# MC21R01_Inverter_2.net
KiCad netlist of a schematic drawn in Altium Designer
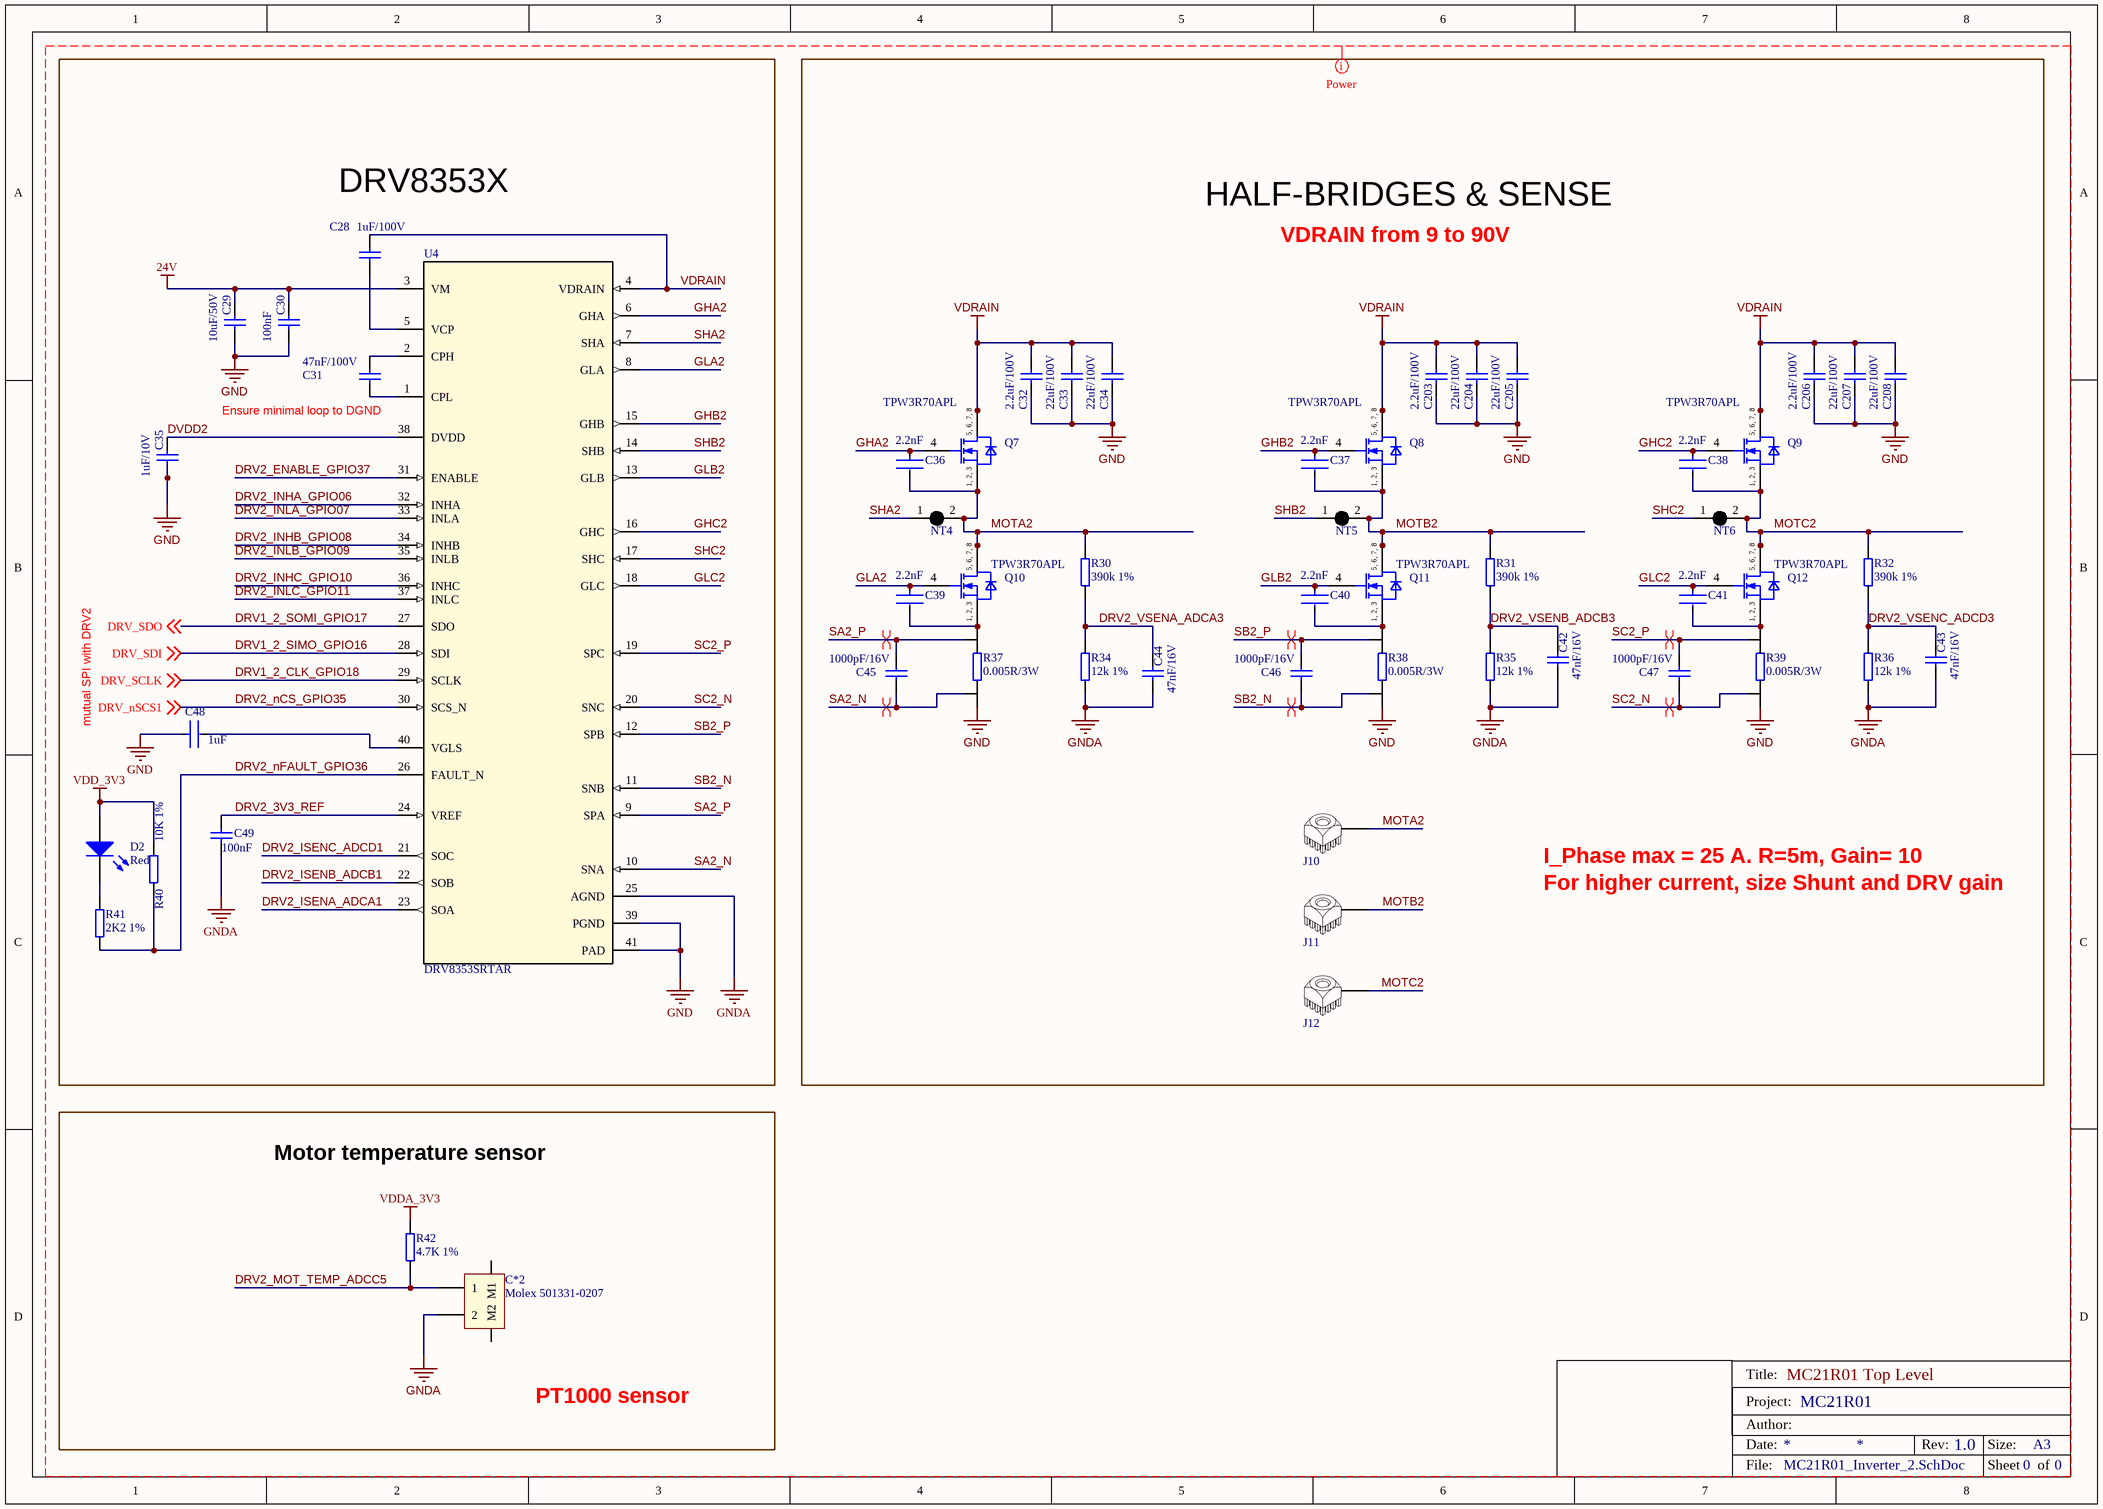
[diagram p0: MC21R01_Inverter_2.SchDoc]

(export (version "E")
  (design (tool "Eeschema 10.0.6"))
  (components
    (comp (ref "C*2")
      (value "Molex 501331-0207")
      (footprint "Molex 501331-0207")
      (description "PicoClasp 02 pin vertical")
      (libsource (lib "PAL_Molex") (part "Molex 501331-0207"))
    )
    (comp (ref "C28")
      (value "1uF/100V")
      (footprint "PAL_Capacitors:0805 SMD capacitor")
      (description "1 uF 100 V 0805  ±10% Tolerance X7R Multilayer Ceramic Chip Capacitor")
      (fields (field (name "Comment") "1uF/100V 0805 10% X7R"))
      (libsource (lib "PAL_Capacitors") (part "1uF/100V 0805 10% X7R"))
    )
    (comp (ref "C29")
      (value "10uF/50V")
      (footprint "PAL_Capacitors:1206 SMD Capacitor")
      (description "10 uF 50 V 1206 ±20% Tolerance X5R Multilayer Ceramic Chip Capacitor")
      (fields (field (name "Comment") "10uf/50V 1206 20% X5R"))
      (libsource (lib "PAL_Capacitors") (part "10uF/50V 1206 20% X5R"))
    )
    (comp (ref "C30")
      (value "100nF")
      (footprint "CAPC0603X03N")
      (description "100nF/25V 0201 10% Tolerance X6S Multilayer Ceramic Chip Capacitor")
      (fields (field (name "TOLERANCE") "10%") (field (name "Comment") "100nF/25V 0201 10% X6S"))
      (libsource (lib "Wandercraft") (part "STD_CAP_2PIN_NPOL"))
    )
    (comp (ref "C31")
      (value "47nF/100V")
      (footprint "PAL_Capacitors:0603 SMD capacitor")
      (description "47 nF 100 V 0603 ±10% Tolerance X7R Multilayer Ceramic Chip Capacitor")
      (fields (field (name "Comment") "47nF/100V 0603 10% X7R"))
      (libsource (lib "PAL_Capacitors") (part "47nF/100V 0603 10% X7R_1"))
    )
    (comp (ref "C32")
      (value "2.2uF/100V")
      (footprint "1210 SMD capacitor h=2mm")
      (description "2.2 uF 100 V 1210  ±10% Tolerance X7R Multilayer Ceramic Chip Capacitor")
      (fields (field (name "Comment") "2.2uF/100V 1210 10% X7R"))
      (libsource (lib "PAL_Capacitors") (part "2.2uF/100V 1210 10% X7R"))
    )
    (comp (ref "C33")
      (value "22uF/100V")
      (footprint "PAL_Capacitors:2220 SMD Capacitor H=5MM")
      (description "22 uF 100 V 2220 ±20% Tolerance X7S Multilayer Ceramic Chip Capacitor")
      (fields (field (name "Comment") "22uF/100V 2220 20% X7S"))
      (libsource (lib "PAL_Capacitors") (part "22uF/100V 2220 20% X7S"))
    )
    (comp (ref "C34")
      (value "22uF/100V")
      (footprint "PAL_Capacitors:2220 SMD Capacitor H=5MM")
      (description "22 uF 100 V 2220 ±20% Tolerance X7S Multilayer Ceramic Chip Capacitor")
      (fields (field (name "Comment") "22uF/100V 2220 20% X7S"))
      (libsource (lib "PAL_Capacitors") (part "22uF/100V 2220 20% X7S"))
    )
    (comp (ref "C35")
      (value "1uF/10V")
      (footprint "PAL_Capacitors:0603 SMD capacitor")
      (description "1uF/10V 0603 10% Tolerance X7R Multilayer Ceramic Chip Capacitor")
      (fields (field (name "Comment") "1uF/10V 0603 10% X7R"))
      (libsource (lib "PAL_Capacitors") (part "1uF/10V 0603 10% X7R"))
    )
    (comp (ref "C36")
      (value "2200pF/50V 0201 10% X7R")
      (footprint "FP-GRM033-0_03-IPC_A")
      (description "2200pF/50V 0201 10% Tolerance X7R Multilayer Ceramic Chip Capacitor")
      (fields (field (name "TOLERANCE") "10%") (field (name "CAPACITANCE") "2.2nF"))
      (libsource (lib "Altium Content Vault") (part "b4654b650e69147ec39a6b967a45e02"))
    )
    (comp (ref "C37")
      (value "2200pF/50V 0201 10% X7R")
      (footprint "FP-GRM033-0_03-IPC_A")
      (description "2200pF/50V 0201 10% Tolerance X7R Multilayer Ceramic Chip Capacitor")
      (fields (field (name "TOLERANCE") "10%") (field (name "CAPACITANCE") "2.2nF"))
      (libsource (lib "Altium Content Vault") (part "b4654b650e69147ec39a6b967a45e02"))
    )
    (comp (ref "C38")
      (value "2200pF/50V 0201 10% X7R")
      (footprint "FP-GRM033-0_03-IPC_A")
      (description "2200pF/50V 0201 10% Tolerance X7R Multilayer Ceramic Chip Capacitor")
      (fields (field (name "TOLERANCE") "10%") (field (name "CAPACITANCE") "2.2nF"))
      (libsource (lib "Altium Content Vault") (part "b4654b650e69147ec39a6b967a45e02"))
    )
    (comp (ref "C39")
      (value "2200pF/50V 0201 10% X7R")
      (footprint "FP-GRM033-0_03-IPC_A")
      (description "2200pF/50V 0201 10% Tolerance X7R Multilayer Ceramic Chip Capacitor")
      (fields (field (name "TOLERANCE") "10%") (field (name "CAPACITANCE") "2.2nF"))
      (libsource (lib "Altium Content Vault") (part "b4654b650e69147ec39a6b967a45e02"))
    )
    (comp (ref "C40")
      (value "2200pF/50V 0201 10% X7R")
      (footprint "FP-GRM033-0_03-IPC_A")
      (description "2200pF/50V 0201 10% Tolerance X7R Multilayer Ceramic Chip Capacitor")
      (fields (field (name "TOLERANCE") "10%") (field (name "CAPACITANCE") "2.2nF"))
      (libsource (lib "Altium Content Vault") (part "b4654b650e69147ec39a6b967a45e02"))
    )
    (comp (ref "C41")
      (value "2200pF/50V 0201 10% X7R")
      (footprint "FP-GRM033-0_03-IPC_A")
      (description "2200pF/50V 0201 10% Tolerance X7R Multilayer Ceramic Chip Capacitor")
      (fields (field (name "TOLERANCE") "10%") (field (name "CAPACITANCE") "2.2nF"))
      (libsource (lib "Altium Content Vault") (part "b4654b650e69147ec39a6b967a45e02"))
    )
    (comp (ref "C42")
      (value "47nF/16V")
      (footprint "PAL_Capacitors:0402 SMD Capacitor")
      (description "47nF/16V 0402 10% Tolerance X7R Multilayer Ceramic Chip Capacitor")
      (fields (field (name "Comment") "47nF/16V 0402 10% X7R"))
      (libsource (lib "PAL_Capacitors") (part "47nF/16V 0402 10% X7R"))
    )
    (comp (ref "C43")
      (value "47nF/16V")
      (footprint "PAL_Capacitors:0402 SMD Capacitor")
      (description "47nF/16V 0402 10% Tolerance X7R Multilayer Ceramic Chip Capacitor")
      (fields (field (name "Comment") "47nF/16V 0402 10% X7R"))
      (libsource (lib "PAL_Capacitors") (part "47nF/16V 0402 10% X7R"))
    )
    (comp (ref "C44")
      (value "47nF/16V")
      (footprint "PAL_Capacitors:0402 SMD Capacitor")
      (description "47nF/16V 0402 10% Tolerance X7R Multilayer Ceramic Chip Capacitor")
      (fields (field (name "Comment") "47nF/16V 0402 10% X7R"))
      (libsource (lib "PAL_Capacitors") (part "47nF/16V 0402 10% X7R"))
    )
    (comp (ref "C45")
      (value "1000pF/16V")
      (footprint "PAL_Capacitors:0402 SMD Capacitor")
      (description "1000pF/16V 0402 10% Tolerance X7R Multilayer Ceramic Chip Capacitor")
      (fields (field (name "Comment") "1000pF/16V 0402 10% X7R"))
      (libsource (lib "PAL_Capacitors") (part "1000pF/16V 0402 10% X7R_1"))
    )
    (comp (ref "C46")
      (value "1000pF/16V")
      (footprint "PAL_Capacitors:0402 SMD Capacitor")
      (description "1000pF/16V 0402 10% Tolerance X7R Multilayer Ceramic Chip Capacitor")
      (fields (field (name "Comment") "1000pF/16V 0402 10% X7R"))
      (libsource (lib "PAL_Capacitors") (part "1000pF/16V 0402 10% X7R_1"))
    )
    (comp (ref "C47")
      (value "1000pF/16V")
      (footprint "PAL_Capacitors:0402 SMD Capacitor")
      (description "1000pF/16V 0402 10% Tolerance X7R Multilayer Ceramic Chip Capacitor")
      (fields (field (name "Comment") "1000pF/16V 0402 10% X7R"))
      (libsource (lib "PAL_Capacitors") (part "1000pF/16V 0402 10% X7R_1"))
    )
    (comp (ref "C48")
      (value "1uF/6.3V 0201 10% X5R")
      (footprint "FP-CL03-IPC_A")
      (description "1uF/6.3V 0201 10% Tolerance X5R Multilayer Ceramic Chip Capacitor")
      (fields (field (name "TOLERANCE") "20%") (field (name "CAPACITANCE") "1uF"))
      (libsource (lib "Altium Content Vault") (part "b4654b650e69147ec39a6b967a45e02"))
    )
    (comp (ref "C49")
      (value "100nF")
      (footprint "CAPC0603X03N")
      (description "100nF/25V 0201 10% Tolerance X6S Multilayer Ceramic Chip Capacitor")
      (fields (field (name "TOLERANCE") "10%") (field (name "Comment") "100nF/25V 0201 10% X6S"))
      (libsource (lib "Wandercraft") (part "STD_CAP_2PIN_NPOL"))
    )
    (comp (ref "C203")
      (value "2.2uF/100V")
      (footprint "1210 SMD capacitor h=2mm")
      (description "2.2 uF 100 V 1210  ±10% Tolerance X7R Multilayer Ceramic Chip Capacitor")
      (fields (field (name "Comment") "2.2uF/100V 1210 10% X7R"))
      (libsource (lib "PAL_Capacitors") (part "2.2uF/100V 1210 10% X7R"))
    )
    (comp (ref "C204")
      (value "22uF/100V")
      (footprint "PAL_Capacitors:2220 SMD Capacitor H=5MM")
      (description "22 uF 100 V 2220 ±20% Tolerance X7S Multilayer Ceramic Chip Capacitor")
      (fields (field (name "Comment") "22uF/100V 2220 20% X7S"))
      (libsource (lib "PAL_Capacitors") (part "22uF/100V 2220 20% X7S"))
    )
    (comp (ref "C205")
      (value "22uF/100V")
      (footprint "PAL_Capacitors:2220 SMD Capacitor H=5MM")
      (description "22 uF 100 V 2220 ±20% Tolerance X7S Multilayer Ceramic Chip Capacitor")
      (fields (field (name "Comment") "22uF/100V 2220 20% X7S"))
      (libsource (lib "PAL_Capacitors") (part "22uF/100V 2220 20% X7S"))
    )
    (comp (ref "C206")
      (value "2.2uF/100V")
      (footprint "1210 SMD capacitor h=2mm")
      (description "2.2 uF 100 V 1210  ±10% Tolerance X7R Multilayer Ceramic Chip Capacitor")
      (fields (field (name "Comment") "2.2uF/100V 1210 10% X7R"))
      (libsource (lib "PAL_Capacitors") (part "2.2uF/100V 1210 10% X7R"))
    )
    (comp (ref "C207")
      (value "22uF/100V")
      (footprint "PAL_Capacitors:2220 SMD Capacitor H=5MM")
      (description "22 uF 100 V 2220 ±20% Tolerance X7S Multilayer Ceramic Chip Capacitor")
      (fields (field (name "Comment") "22uF/100V 2220 20% X7S"))
      (libsource (lib "PAL_Capacitors") (part "22uF/100V 2220 20% X7S"))
    )
    (comp (ref "C208")
      (value "22uF/100V")
      (footprint "PAL_Capacitors:2220 SMD Capacitor H=5MM")
      (description "22 uF 100 V 2220 ±20% Tolerance X7S Multilayer Ceramic Chip Capacitor")
      (fields (field (name "Comment") "22uF/100V 2220 20% X7S"))
      (libsource (lib "PAL_Capacitors") (part "22uF/100V 2220 20% X7S"))
    )
    (comp (ref "D2")
      (value "Red")
      (footprint "0402 SMD LED Red")
      (description "Low Profile Chip LED, Red")
      (fields (field (name "MANUFACTURER") "ROHM") (field (name "MANUFACTURER PART NUMBER") "SML-P11UTT86R"))
      (libsource (lib "PAL_devices") (part "LED_0402_Red"))
    )
    (comp (ref "J10")
      (value "WE_7461094")
      (footprint "WE_7461094")
      (description "REDCUBE PRESS-FIT with external thread and full plain pin-plate WPSHFU, 130A, M3 screw, 9pins")
      (fields
        (field (name "MANUFACTURER") "WURTH ELEKTRONIK")
        (field (name "MANUFACTURER PART NUMBER") "7461094")
        (field (name "CREATED BY") "Yaiza Montes")
      )
      (libsource (lib "PAL_Wurth_2020") (part "WE_7461094"))
    )
    (comp (ref "J11")
      (value "WE_7461094")
      (footprint "WE_7461094")
      (description "REDCUBE PRESS-FIT with external thread and full plain pin-plate WPSHFU, 130A, M3 screw, 9pins")
      (fields
        (field (name "MANUFACTURER") "WURTH ELEKTRONIK")
        (field (name "MANUFACTURER PART NUMBER") "7461094")
        (field (name "CREATED BY") "Yaiza Montes")
      )
      (libsource (lib "PAL_Wurth_2020") (part "WE_7461094"))
    )
    (comp (ref "J12")
      (value "WE_7461094")
      (footprint "WE_7461094")
      (description "REDCUBE PRESS-FIT with external thread and full plain pin-plate WPSHFU, 130A, M3 screw, 9pins")
      (fields
        (field (name "MANUFACTURER") "WURTH ELEKTRONIK")
        (field (name "MANUFACTURER PART NUMBER") "7461094")
        (field (name "CREATED BY") "Yaiza Montes")
      )
      (libsource (lib "PAL_Wurth_2020") (part "WE_7461094"))
    )
    (comp (ref "NT4")
      (value "Net Tie SMD")
      (footprint "PAL_devices:Net Tie SMD 0.4x0.8mm")
      (description "Net Tie starpoint")
      (libsource (lib "PAL_devices") (part "Net Tie SMD"))
    )
    (comp (ref "NT5")
      (value "Net Tie SMD")
      (footprint "PAL_devices:Net Tie SMD 0.4x0.8mm")
      (description "Net Tie starpoint")
      (libsource (lib "PAL_devices") (part "Net Tie SMD"))
    )
    (comp (ref "NT6")
      (value "Net Tie SMD")
      (footprint "PAL_devices:Net Tie SMD 0.4x0.8mm")
      (description "Net Tie starpoint")
      (libsource (lib "PAL_devices") (part "Net Tie SMD"))
    )
    (comp (ref "Q7")
      (value "TPW3R70APL")
      (footprint "DSOP Advance Toshiba")
      (description "Silicon N-channel MOS (U-MOS-H)")
      (fields (field (name "MANUFACTURER") "Toshiba Semicon"))
      (libsource (lib "PAL_devices") (part "TPW3R70APL"))
    )
    (comp (ref "Q8")
      (value "TPW3R70APL")
      (footprint "DSOP Advance Toshiba")
      (description "Silicon N-channel MOS (U-MOS-H)")
      (fields (field (name "MANUFACTURER") "Toshiba Semicon"))
      (libsource (lib "PAL_devices") (part "TPW3R70APL"))
    )
    (comp (ref "Q9")
      (value "TPW3R70APL")
      (footprint "DSOP Advance Toshiba")
      (description "Silicon N-channel MOS (U-MOS-H)")
      (fields (field (name "MANUFACTURER") "Toshiba Semicon"))
      (libsource (lib "PAL_devices") (part "TPW3R70APL"))
    )
    (comp (ref "Q10")
      (value "TPW3R70APL")
      (footprint "DSOP Advance Toshiba")
      (description "Silicon N-channel MOS (U-MOS-H)")
      (fields (field (name "MANUFACTURER") "Toshiba Semicon"))
      (libsource (lib "PAL_devices") (part "TPW3R70APL"))
    )
    (comp (ref "Q11")
      (value "TPW3R70APL")
      (footprint "DSOP Advance Toshiba")
      (description "Silicon N-channel MOS (U-MOS-H)")
      (fields (field (name "MANUFACTURER") "Toshiba Semicon"))
      (libsource (lib "PAL_devices") (part "TPW3R70APL"))
    )
    (comp (ref "Q12")
      (value "TPW3R70APL")
      (footprint "DSOP Advance Toshiba")
      (description "Silicon N-channel MOS (U-MOS-H)")
      (fields (field (name "MANUFACTURER") "Toshiba Semicon"))
      (libsource (lib "PAL_devices") (part "TPW3R70APL"))
    )
    (comp (ref "R30")
      (value "390k 1%")
      (footprint "PAL_Resistors:0603 SMD resistor")
      (description "390k/150V 1% 0603 250mW SMD Resistor")
      (libsource (lib "PAL_Resistors") (part "390k/150V 1% 0603 250mW"))
    )
    (comp (ref "R31")
      (value "390k 1%")
      (footprint "PAL_Resistors:0603 SMD resistor")
      (description "390k/150V 1% 0603 250mW SMD Resistor")
      (libsource (lib "PAL_Resistors") (part "390k/150V 1% 0603 250mW"))
    )
    (comp (ref "R32")
      (value "390k 1%")
      (footprint "PAL_Resistors:0603 SMD resistor")
      (description "390k/150V 1% 0603 250mW SMD Resistor")
      (libsource (lib "PAL_Resistors") (part "390k/150V 1% 0603 250mW"))
    )
    (comp (ref "R34")
      (value "12k 1%")
      (footprint "PAL_Resistors:0603 SMD resistor")
      (description "12k/150V 1% 0603 250mW SMD Resistor")
      (libsource (lib "PAL_Resistors") (part "12k/150V 1% 0603 250mW"))
    )
    (comp (ref "R35")
      (value "12k 1%")
      (footprint "PAL_Resistors:0603 SMD resistor")
      (description "12k/150V 1% 0603 250mW SMD Resistor")
      (libsource (lib "PAL_Resistors") (part "12k/150V 1% 0603 250mW"))
    )
    (comp (ref "R36")
      (value "12k 1%")
      (footprint "PAL_Resistors:0603 SMD resistor")
      (description "12k/150V 1% 0603 250mW SMD Resistor")
      (libsource (lib "PAL_Resistors") (part "12k/150V 1% 0603 250mW"))
    )
    (comp (ref "R37")
      (value "0.005R/3W")
      (footprint "PAL_Resistors:2512 SMD Resistor V2 NETTIE")
      (description "0.005R/3W 1% 2512 shunt SMD Resistor")
      (libsource (lib "PAL_Resistors") (part "0.005R/3W 1% 2512 Shunt"))
    )
    (comp (ref "R38")
      (value "0.005R/3W")
      (footprint "PAL_Resistors:2512 SMD Resistor V2 NETTIE")
      (description "0.005R/3W 1% 2512 shunt SMD Resistor")
      (libsource (lib "PAL_Resistors") (part "0.005R/3W 1% 2512 Shunt"))
    )
    (comp (ref "R39")
      (value "0.005R/3W")
      (footprint "PAL_Resistors:2512 SMD Resistor V2 NETTIE")
      (description "0.005R/3W 1% 2512 shunt SMD Resistor")
      (libsource (lib "PAL_Resistors") (part "0.005R/3W 1% 2512 Shunt"))
    )
    (comp (ref "R40")
      (value "10K 1%")
      (footprint "0402 SMD rESISTOR")
      (description "10K/50V 1% 0402 100mW SMD Resistor")
      (libsource (lib "PAL_Resistors") (part "10K/50V 1% 0402 100mW"))
    )
    (comp (ref "R41")
      (value "2K2 1%")
      (footprint "0402 SMD rESISTOR")
      (description "2K2/50V 1% 0402 100mW SMD Resistor")
      (libsource (lib "PAL_Resistors") (part "2K2/50V 1% 0402 100mW"))
    )
    (comp (ref "R42")
      (value "4.7K 1%")
      (footprint "0402 SMD rESISTOR")
      (description "4.7K/50V 1% 0402 100mW SMD Resistor")
      (libsource (lib "PAL_Resistors") (part "4.7K/50V 1% 0402 100mW"))
    )
    (comp (ref "U4")
      (value "DRV8353SRTAR")
      (footprint "PAL_IPC-7351B_Footprints:QFN50P600X600X80_HS-41N")
      (description "102-V max 3-phase smart gate driver with current shunt amplifiers")
      (fields (field (name "MANUFACTURER") "Texas Instruments"))
      (libsource (lib "PAL_devices") (part "DRV8353SRTAR"))
    )
  )
  (nets
    (net (code "1") (name "/DRV2_3V3_REF") (class "Default")
      (node (ref "C49") (pin "2") (pinfunction "2_2") (pintype "passive"))
      (node (ref "U4") (pin "24") (pinfunction "VREF_24") (pintype "input"))
    )
    (net (code "2") (name "/DRV2_ENABLE_GPIO37") (class "Default")
      (node (ref "U4") (pin "31") (pinfunction "ENABLE_31") (pintype "input"))
    )
    (net (code "3") (name "/DRV2_INHA_GPIO06") (class "Default")
      (node (ref "U4") (pin "32") (pinfunction "INHA_32") (pintype "input"))
    )
    (net (code "4") (name "/DRV2_INHB_GPIO08") (class "Default")
      (node (ref "U4") (pin "34") (pinfunction "INHB_34") (pintype "input"))
    )
    (net (code "5") (name "/DRV2_INHC_GPIO10") (class "Default")
      (node (ref "U4") (pin "36") (pinfunction "INHC_36") (pintype "input"))
    )
    (net (code "6") (name "/DRV2_INLA_GPIO07") (class "Default")
      (node (ref "U4") (pin "33") (pinfunction "INLA_33") (pintype "input"))
    )
    (net (code "7") (name "/DRV2_INLB_GPIO09") (class "Default")
      (node (ref "U4") (pin "35") (pinfunction "INLB_35") (pintype "input"))
    )
    (net (code "8") (name "/DRV2_INLC_GPIO11") (class "Default")
      (node (ref "U4") (pin "37") (pinfunction "INLC_37") (pintype "input"))
    )
    (net (code "9") (name "/DRV2_ISENA_ADCA1") (class "Default")
      (node (ref "U4") (pin "23") (pinfunction "SOA_23") (pintype "output"))
    )
    (net (code "10") (name "/DRV2_ISENB_ADCB1") (class "Default")
      (node (ref "U4") (pin "22") (pinfunction "SOB_22") (pintype "output"))
    )
    (net (code "11") (name "/DRV2_ISENC_ADCD1") (class "Default")
      (node (ref "U4") (pin "21") (pinfunction "SOC_21") (pintype "output"))
    )
    (net (code "12") (name "/DRV2_MOT_TEMP_ADCC5") (class "Default")
      (node (ref "C*2") (pin "1") (pinfunction "1_1") (pintype "passive"))
      (node (ref "R42") (pin "1") (pinfunction "1_1") (pintype "passive"))
    )
    (net (code "13") (name "/DRV2_VSENA_ADCA3") (class "Default")
      (node (ref "C44") (pin "1") (pinfunction "1_1") (pintype "passive"))
      (node (ref "R30") (pin "1") (pinfunction "1_1") (pintype "passive"))
      (node (ref "R34") (pin "2") (pinfunction "2_2") (pintype "passive"))
    )
    (net (code "14") (name "/DRV2_VSENB_ADCB3") (class "Default")
      (node (ref "C42") (pin "1") (pinfunction "1_1") (pintype "passive"))
      (node (ref "R31") (pin "1") (pinfunction "1_1") (pintype "passive"))
      (node (ref "R35") (pin "2") (pinfunction "2_2") (pintype "passive"))
    )
    (net (code "15") (name "/DRV2_VSENC_ADCD3") (class "Default")
      (node (ref "C43") (pin "1") (pinfunction "1_1") (pintype "passive"))
      (node (ref "R32") (pin "1") (pinfunction "1_1") (pintype "passive"))
      (node (ref "R36") (pin "2") (pinfunction "2_2") (pintype "passive"))
    )
    (net (code "16") (name "/DRV2_nFAULT_GPIO36") (class "Default")
      (node (ref "R40") (pin "1") (pinfunction "1_1") (pintype "passive"))
      (node (ref "R41") (pin "1") (pinfunction "1_1") (pintype "passive"))
      (node (ref "U4") (pin "26") (pinfunction "FAULT_N_26") (pintype "open_collector"))
    )
    (net (code "17") (name "/DVDD2") (class "Default")
      (node (ref "C35") (pin "1") (pinfunction "1_1") (pintype "passive"))
      (node (ref "U4") (pin "38") (pinfunction "DVDD_38") (pintype "power_in"))
    )
    (net (code "18") (name "/GHA2") (class "Default")
      (node (ref "C36") (pin "1") (pinfunction "1_1") (pintype "passive"))
      (node (ref "Q7") (pin "4") (pinfunction "GATE_4") (pintype "passive"))
      (node (ref "U4") (pin "6") (pinfunction "GHA_6") (pintype "output"))
    )
    (net (code "19") (name "/GHB2") (class "Default")
      (node (ref "C37") (pin "1") (pinfunction "1_1") (pintype "passive"))
      (node (ref "Q8") (pin "4") (pinfunction "GATE_4") (pintype "passive"))
      (node (ref "U4") (pin "15") (pinfunction "GHB_15") (pintype "output"))
    )
    (net (code "20") (name "/GHC2") (class "Default")
      (node (ref "C38") (pin "1") (pinfunction "1_1") (pintype "passive"))
      (node (ref "Q9") (pin "4") (pinfunction "GATE_4") (pintype "passive"))
      (node (ref "U4") (pin "16") (pinfunction "GHC_16") (pintype "output"))
    )
    (net (code "21") (name "/GLA2") (class "Default")
      (node (ref "C39") (pin "1") (pinfunction "1_1") (pintype "passive"))
      (node (ref "Q10") (pin "4") (pinfunction "GATE_4") (pintype "passive"))
      (node (ref "U4") (pin "8") (pinfunction "GLA_8") (pintype "output"))
    )
    (net (code "22") (name "/GLB2") (class "Default")
      (node (ref "C40") (pin "1") (pinfunction "1_1") (pintype "passive"))
      (node (ref "Q11") (pin "4") (pinfunction "GATE_4") (pintype "passive"))
      (node (ref "U4") (pin "13") (pinfunction "GLB_13") (pintype "output"))
    )
    (net (code "23") (name "/GLC2") (class "Default")
      (node (ref "C41") (pin "1") (pinfunction "1_1") (pintype "passive"))
      (node (ref "Q12") (pin "4") (pinfunction "GATE_4") (pintype "passive"))
      (node (ref "U4") (pin "18") (pinfunction "GLC_18") (pintype "output"))
    )
    (net (code "24") (name "/MOTA2") (class "Default")
      (node (ref "C36") (pin "2") (pinfunction "2_2") (pintype "passive"))
      (node (ref "J10") (pin "1") (pinfunction "1_1") (pintype "passive"))
      (node (ref "NT4") (pin "2") (pinfunction "2_2") (pintype "passive"))
      (node (ref "Q10") (pin "5") (pinfunction "DRAIN_5") (pintype "passive"))
      (node (ref "Q10") (pin "6") (pinfunction "DRAIN_6") (pintype "passive"))
      (node (ref "Q10") (pin "7") (pinfunction "DRAIN_7") (pintype "passive"))
      (node (ref "Q10") (pin "8") (pinfunction "DRAIN_8") (pintype "passive"))
      (node (ref "Q7") (pin "1") (pinfunction "SOURCE_1") (pintype "passive"))
      (node (ref "Q7") (pin "2") (pinfunction "SOURCE_2") (pintype "passive"))
      (node (ref "Q7") (pin "3") (pinfunction "SOURCE_3") (pintype "passive"))
      (node (ref "R30") (pin "2") (pinfunction "2_2") (pintype "passive"))
    )
    (net (code "25") (name "/MOTB2") (class "Default")
      (node (ref "C37") (pin "2") (pinfunction "2_2") (pintype "passive"))
      (node (ref "J11") (pin "1") (pinfunction "1_1") (pintype "passive"))
      (node (ref "NT5") (pin "2") (pinfunction "2_2") (pintype "passive"))
      (node (ref "Q11") (pin "5") (pinfunction "DRAIN_5") (pintype "passive"))
      (node (ref "Q11") (pin "6") (pinfunction "DRAIN_6") (pintype "passive"))
      (node (ref "Q11") (pin "7") (pinfunction "DRAIN_7") (pintype "passive"))
      (node (ref "Q11") (pin "8") (pinfunction "DRAIN_8") (pintype "passive"))
      (node (ref "Q8") (pin "1") (pinfunction "SOURCE_1") (pintype "passive"))
      (node (ref "Q8") (pin "2") (pinfunction "SOURCE_2") (pintype "passive"))
      (node (ref "Q8") (pin "3") (pinfunction "SOURCE_3") (pintype "passive"))
      (node (ref "R31") (pin "2") (pinfunction "2_2") (pintype "passive"))
    )
    (net (code "26") (name "/MOTC2") (class "Default")
      (node (ref "C38") (pin "2") (pinfunction "2_2") (pintype "passive"))
      (node (ref "J12") (pin "1") (pinfunction "1_1") (pintype "passive"))
      (node (ref "NT6") (pin "2") (pinfunction "2_2") (pintype "passive"))
      (node (ref "Q12") (pin "5") (pinfunction "DRAIN_5") (pintype "passive"))
      (node (ref "Q12") (pin "6") (pinfunction "DRAIN_6") (pintype "passive"))
      (node (ref "Q12") (pin "7") (pinfunction "DRAIN_7") (pintype "passive"))
      (node (ref "Q12") (pin "8") (pinfunction "DRAIN_8") (pintype "passive"))
      (node (ref "Q9") (pin "1") (pinfunction "SOURCE_1") (pintype "passive"))
      (node (ref "Q9") (pin "2") (pinfunction "SOURCE_2") (pintype "passive"))
      (node (ref "Q9") (pin "3") (pinfunction "SOURCE_3") (pintype "passive"))
      (node (ref "R32") (pin "2") (pinfunction "2_2") (pintype "passive"))
    )
    (net (code "27") (name "/SA2_N") (class "Default")
      (node (ref "C45") (pin "2") (pinfunction "2_2") (pintype "passive"))
      (node (ref "R37") (pin "3") (pinfunction "3_3") (pintype "passive"))
      (node (ref "U4") (pin "10") (pinfunction "SNA_10") (pintype "input"))
    )
    (net (code "28") (name "/SA2_P") (class "Default")
      (node (ref "C45") (pin "1") (pinfunction "1_1") (pintype "passive"))
      (node (ref "R37") (pin "4") (pinfunction "4_4") (pintype "passive"))
      (node (ref "U4") (pin "9") (pinfunction "SPA_9") (pintype "input"))
    )
    (net (code "29") (name "/SB2_N") (class "Default")
      (node (ref "C46") (pin "2") (pinfunction "2_2") (pintype "passive"))
      (node (ref "R38") (pin "3") (pinfunction "3_3") (pintype "passive"))
      (node (ref "U4") (pin "11") (pinfunction "SNB_11") (pintype "input"))
    )
    (net (code "30") (name "/SB2_P") (class "Default")
      (node (ref "C46") (pin "1") (pinfunction "1_1") (pintype "passive"))
      (node (ref "R38") (pin "4") (pinfunction "4_4") (pintype "passive"))
      (node (ref "U4") (pin "12") (pinfunction "SPB_12") (pintype "input"))
    )
    (net (code "31") (name "/SC2_N") (class "Default")
      (node (ref "C47") (pin "2") (pinfunction "2_2") (pintype "passive"))
      (node (ref "R39") (pin "3") (pinfunction "3_3") (pintype "passive"))
      (node (ref "U4") (pin "20") (pinfunction "SNC_20") (pintype "input"))
    )
    (net (code "32") (name "/SC2_P") (class "Default")
      (node (ref "C47") (pin "1") (pinfunction "1_1") (pintype "passive"))
      (node (ref "R39") (pin "4") (pinfunction "4_4") (pintype "passive"))
      (node (ref "U4") (pin "19") (pinfunction "SPC_19") (pintype "input"))
    )
    (net (code "33") (name "/SHA2") (class "Default")
      (node (ref "NT4") (pin "1") (pinfunction "1_1") (pintype "passive"))
      (node (ref "U4") (pin "7") (pinfunction "SHA_7") (pintype "input"))
    )
    (net (code "34") (name "/SHB2") (class "Default")
      (node (ref "NT5") (pin "1") (pinfunction "1_1") (pintype "passive"))
      (node (ref "U4") (pin "14") (pinfunction "SHB_14") (pintype "input"))
    )
    (net (code "35") (name "/SHC2") (class "Default")
      (node (ref "NT6") (pin "1") (pinfunction "1_1") (pintype "passive"))
      (node (ref "U4") (pin "17") (pinfunction "SHC_17") (pintype "input"))
    )
    (net (code "36") (name "24V") (class "Default")
      (node (ref "C29") (pin "1") (pinfunction "1_1") (pintype "passive"))
      (node (ref "C30") (pin "2") (pinfunction "2_2") (pintype "passive"))
      (node (ref "U4") (pin "3") (pinfunction "VM_3") (pintype "power_in"))
    )
    (net (code "37") (name "DRV_SCLK") (class "Default")
      (node (ref "U4") (pin "29") (pinfunction "SCLK_29") (pintype "input"))
    )
    (net (code "38") (name "DRV_SDI") (class "Default")
      (node (ref "U4") (pin "28") (pinfunction "SDI_28") (pintype "input"))
    )
    (net (code "39") (name "DRV_SDO") (class "Default")
      (node (ref "U4") (pin "27") (pinfunction "SDO_27") (pintype "passive"))
    )
    (net (code "40") (name "DRV_nSCS1") (class "Default")
      (node (ref "U4") (pin "30") (pinfunction "SCS_N_30") (pintype "input"))
    )
    (net (code "41") (name "GND") (class "Default")
      (node (ref "C203") (pin "2") (pinfunction "2_2") (pintype "passive"))
      (node (ref "C204") (pin "2") (pinfunction "2_2") (pintype "passive"))
      (node (ref "C205") (pin "2") (pinfunction "2_2") (pintype "passive"))
      (node (ref "C206") (pin "2") (pinfunction "2_2") (pintype "passive"))
      (node (ref "C207") (pin "2") (pinfunction "2_2") (pintype "passive"))
      (node (ref "C208") (pin "2") (pinfunction "2_2") (pintype "passive"))
      (node (ref "C29") (pin "2") (pinfunction "2_2") (pintype "passive"))
      (node (ref "C30") (pin "1") (pinfunction "1_1") (pintype "passive"))
      (node (ref "C32") (pin "2") (pinfunction "2_2") (pintype "passive"))
      (node (ref "C33") (pin "2") (pinfunction "2_2") (pintype "passive"))
      (node (ref "C34") (pin "2") (pinfunction "2_2") (pintype "passive"))
      (node (ref "C35") (pin "2") (pinfunction "2_2") (pintype "passive"))
      (node (ref "C48") (pin "1") (pinfunction "1_1") (pintype "passive"))
      (node (ref "R37") (pin "1") (pinfunction "1_1") (pintype "passive"))
      (node (ref "R38") (pin "1") (pinfunction "1_1") (pintype "passive"))
      (node (ref "R39") (pin "1") (pinfunction "1_1") (pintype "passive"))
      (node (ref "U4") (pin "39") (pinfunction "PGND_39") (pintype "power_in"))
      (node (ref "U4") (pin "41") (pinfunction "PAD_41") (pintype "power_in"))
    )
    (net (code "42") (name "GNDA") (class "Default")
      (node (ref "C*2") (pin "2") (pinfunction "2_2") (pintype "passive"))
      (node (ref "C42") (pin "2") (pinfunction "2_2") (pintype "passive"))
      (node (ref "C43") (pin "2") (pinfunction "2_2") (pintype "passive"))
      (node (ref "C44") (pin "2") (pinfunction "2_2") (pintype "passive"))
      (node (ref "C49") (pin "1") (pinfunction "1_1") (pintype "passive"))
      (node (ref "R34") (pin "1") (pinfunction "1_1") (pintype "passive"))
      (node (ref "R35") (pin "1") (pinfunction "1_1") (pintype "passive"))
      (node (ref "R36") (pin "1") (pinfunction "1_1") (pintype "passive"))
      (node (ref "U4") (pin "25") (pinfunction "AGND_25") (pintype "power_in"))
    )
    (net (code "43") (name "Net-(C39-Pad2)") (class "Default")
      (node (ref "C39") (pin "2") (pinfunction "2_2") (pintype "passive"))
      (node (ref "Q10") (pin "1") (pinfunction "SOURCE_1") (pintype "passive"))
      (node (ref "Q10") (pin "2") (pinfunction "SOURCE_2") (pintype "passive"))
      (node (ref "Q10") (pin "3") (pinfunction "SOURCE_3") (pintype "passive"))
      (node (ref "R37") (pin "2") (pinfunction "2_2") (pintype "passive"))
    )
    (net (code "44") (name "Net-(C40-Pad2)") (class "Default")
      (node (ref "C40") (pin "2") (pinfunction "2_2") (pintype "passive"))
      (node (ref "Q11") (pin "1") (pinfunction "SOURCE_1") (pintype "passive"))
      (node (ref "Q11") (pin "2") (pinfunction "SOURCE_2") (pintype "passive"))
      (node (ref "Q11") (pin "3") (pinfunction "SOURCE_3") (pintype "passive"))
      (node (ref "R38") (pin "2") (pinfunction "2_2") (pintype "passive"))
    )
    (net (code "45") (name "Net-(C41-Pad2)") (class "Default")
      (node (ref "C41") (pin "2") (pinfunction "2_2") (pintype "passive"))
      (node (ref "Q12") (pin "1") (pinfunction "SOURCE_1") (pintype "passive"))
      (node (ref "Q12") (pin "2") (pinfunction "SOURCE_2") (pintype "passive"))
      (node (ref "Q12") (pin "3") (pinfunction "SOURCE_3") (pintype "passive"))
      (node (ref "R39") (pin "2") (pinfunction "2_2") (pintype "passive"))
    )
    (net (code "46") (name "Net-(D2-PadK)") (class "Default")
      (node (ref "D2") (pin "K") (pinfunction "K_K") (pintype "passive"))
      (node (ref "R41") (pin "2") (pinfunction "2_2") (pintype "passive"))
    )
    (net (code "47") (name "Net-(U4-CPH)") (class "Default")
      (node (ref "C31") (pin "1") (pinfunction "1_1") (pintype "passive"))
      (node (ref "U4") (pin "2") (pinfunction "CPH_2") (pintype "passive"))
    )
    (net (code "48") (name "Net-(U4-CPL)") (class "Default")
      (node (ref "C31") (pin "2") (pinfunction "2_2") (pintype "passive"))
      (node (ref "U4") (pin "1") (pinfunction "CPL_1") (pintype "passive"))
    )
    (net (code "49") (name "Net-(U4-VCP)") (class "Default")
      (node (ref "C28") (pin "2") (pinfunction "2_2") (pintype "passive"))
      (node (ref "U4") (pin "5") (pinfunction "VCP_5") (pintype "power_in"))
    )
    (net (code "50") (name "Net-(U4-VGLS)") (class "Default")
      (node (ref "C48") (pin "2") (pinfunction "2_2") (pintype "passive"))
      (node (ref "U4") (pin "40") (pinfunction "VGLS_40") (pintype "power_in"))
    )
    (net (code "51") (name "VDDA_3V3") (class "Default")
      (node (ref "R42") (pin "2") (pinfunction "2_2") (pintype "passive"))
    )
    (net (code "52") (name "VDD_3V3") (class "Default")
      (node (ref "D2") (pin "A") (pinfunction "A_A") (pintype "passive"))
      (node (ref "R40") (pin "2") (pinfunction "2_2") (pintype "passive"))
    )
    (net (code "53") (name "VDRAIN") (class "Default")
      (node (ref "C203") (pin "1") (pinfunction "1_1") (pintype "passive"))
      (node (ref "C204") (pin "1") (pinfunction "1_1") (pintype "passive"))
      (node (ref "C205") (pin "1") (pinfunction "1_1") (pintype "passive"))
      (node (ref "C206") (pin "1") (pinfunction "1_1") (pintype "passive"))
      (node (ref "C207") (pin "1") (pinfunction "1_1") (pintype "passive"))
      (node (ref "C208") (pin "1") (pinfunction "1_1") (pintype "passive"))
      (node (ref "C28") (pin "1") (pinfunction "1_1") (pintype "passive"))
      (node (ref "C32") (pin "1") (pinfunction "1_1") (pintype "passive"))
      (node (ref "C33") (pin "1") (pinfunction "1_1") (pintype "passive"))
      (node (ref "C34") (pin "1") (pinfunction "1_1") (pintype "passive"))
      (node (ref "Q7") (pin "5") (pinfunction "DRAIN_5") (pintype "passive"))
      (node (ref "Q7") (pin "6") (pinfunction "DRAIN_6") (pintype "passive"))
      (node (ref "Q7") (pin "7") (pinfunction "DRAIN_7") (pintype "passive"))
      (node (ref "Q7") (pin "8") (pinfunction "DRAIN_8") (pintype "passive"))
      (node (ref "Q8") (pin "5") (pinfunction "DRAIN_5") (pintype "passive"))
      (node (ref "Q8") (pin "6") (pinfunction "DRAIN_6") (pintype "passive"))
      (node (ref "Q8") (pin "7") (pinfunction "DRAIN_7") (pintype "passive"))
      (node (ref "Q8") (pin "8") (pinfunction "DRAIN_8") (pintype "passive"))
      (node (ref "Q9") (pin "5") (pinfunction "DRAIN_5") (pintype "passive"))
      (node (ref "Q9") (pin "6") (pinfunction "DRAIN_6") (pintype "passive"))
      (node (ref "Q9") (pin "7") (pinfunction "DRAIN_7") (pintype "passive"))
      (node (ref "Q9") (pin "8") (pinfunction "DRAIN_8") (pintype "passive"))
      (node (ref "U4") (pin "4") (pinfunction "VDRAIN_4") (pintype "input"))
    )
    (net (code "54") (name "unconnected-(C*2-PadM1)") (class "Default")
      (node (ref "C*2") (pin "M1") (pinfunction "M1_M1") (pintype "passive"))
    )
    (net (code "55") (name "unconnected-(C*2-PadM2)") (class "Default")
      (node (ref "C*2") (pin "M2") (pinfunction "M2_M2") (pintype "passive"))
    )
  )
)
